# MCU.net
KiCad netlist of a schematic drawn in Altium Designer
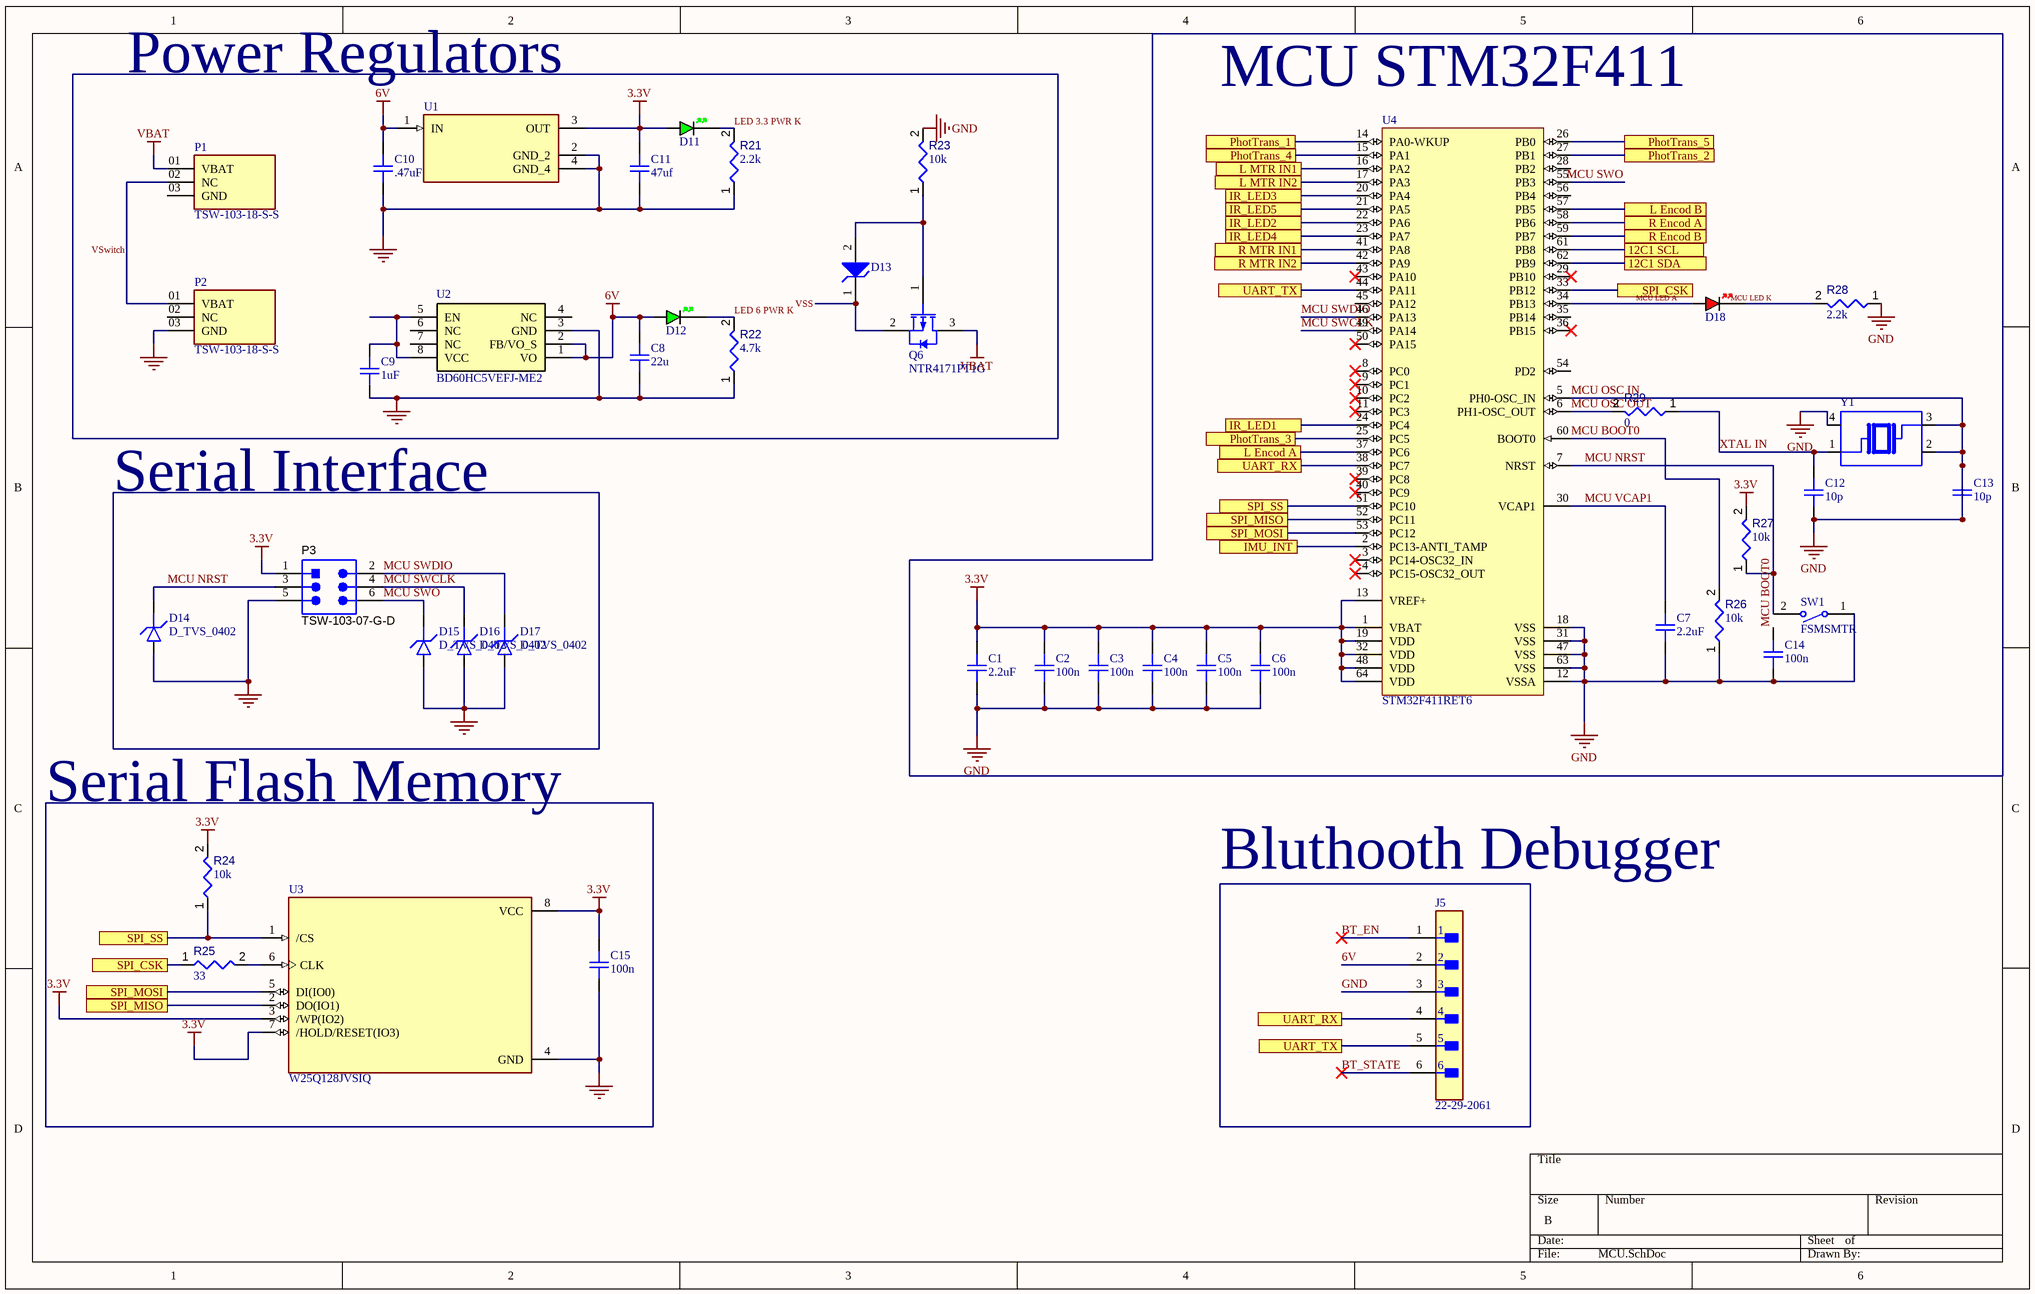
[diagram p0: MCU.SchDoc]

(export (version "E")
  (design (tool "Eeschema 10.0.6"))
  (components
    (comp (ref "C1")
      (value "2.2uF")
      (footprint "CAP_0603")
      (description "Capacitor SMD 0603")
      (libsource (lib "Schematic-Lib-PhilsLab") (part "CAP_0603"))
    )
    (comp (ref "C2")
      (value "100n")
      (footprint "CAP_0603")
      (description "Capacitor SMD 0603")
      (libsource (lib "Schematic-Lib-PhilsLab") (part "CAP_0603"))
    )
    (comp (ref "C3")
      (value "100n")
      (footprint "CAP_0603")
      (description "Capacitor SMD 0603")
      (libsource (lib "Schematic-Lib-PhilsLab") (part "CAP_0603"))
    )
    (comp (ref "C4")
      (value "100n")
      (footprint "CAP_0603")
      (description "Capacitor SMD 0603")
      (libsource (lib "Schematic-Lib-PhilsLab") (part "CAP_0603"))
    )
    (comp (ref "C5")
      (value "100n")
      (footprint "CAP_0603")
      (description "Capacitor SMD 0603")
      (libsource (lib "Schematic-Lib-PhilsLab") (part "CAP_0603"))
    )
    (comp (ref "C6")
      (value "100n")
      (footprint "CAP_0603")
      (description "Capacitor SMD 0603")
      (libsource (lib "Schematic-Lib-PhilsLab") (part "CAP_0603"))
    )
    (comp (ref "C7")
      (value "2.2uF")
      (footprint "CAP_0603")
      (description "Capacitor SMD 0603")
      (libsource (lib "Schematic-Lib-PhilsLab") (part "CAP_0603"))
    )
    (comp (ref "C8")
      (value "22u")
      (footprint "CAP_0805")
      (description "Capacitor SMD 0805")
      (libsource (lib "Schematic-Lib-PhilsLab") (part "CAP_0805"))
    )
    (comp (ref "C9")
      (value "1uF")
      (footprint "CAP_0603")
      (description "Capacitor SMD 0603")
      (libsource (lib "Schematic-Lib-PhilsLab") (part "CAP_0603"))
    )
    (comp (ref "C10")
      (value ".47uF")
      (footprint "CAP_0603")
      (description "Capacitor SMD 0603")
      (libsource (lib "Schematic-Lib-PhilsLab") (part "CAP_0603"))
    )
    (comp (ref "C11")
      (value "47uf")
      (footprint "CAP_1210")
      (description "Capacitor SMD 1210")
      (libsource (lib "Schematic-Lib-PhilsLab") (part "CAP_1210"))
    )
    (comp (ref "C12")
      (value "10p")
      (footprint "CAP_0603")
      (description "Capacitor SMD 0603")
      (libsource (lib "Schematic-Lib-PhilsLab") (part "CAP_0603"))
    )
    (comp (ref "C13")
      (value "10p")
      (footprint "CAP_0603")
      (description "Capacitor SMD 0603")
      (libsource (lib "Schematic-Lib-PhilsLab") (part "CAP_0603"))
    )
    (comp (ref "C14")
      (value "100n")
      (footprint "CAP_0603")
      (description "Capacitor SMD 0603")
      (libsource (lib "Schematic-Lib-PhilsLab") (part "CAP_0603"))
    )
    (comp (ref "C15")
      (value "100n")
      (footprint "CAP_0603")
      (description "Capacitor SMD 0603")
      (libsource (lib "Schematic-Lib-PhilsLab") (part "CAP_0603"))
    )
    (comp (ref "D11")
      (value "GREEN")
      (footprint "LED_0603_GREEN")
      (description "LED 0603 GREEN SMD")
      (libsource (lib "Schematic-Lib-PhilsLab") (part "LED_0603_GREEN"))
    )
    (comp (ref "D12")
      (value "GREEN")
      (footprint "LED_0603_GREEN")
      (description "LED 0603 GREEN SMD")
      (libsource (lib "Schematic-Lib-PhilsLab") (part "LED_0603_GREEN"))
    )
    (comp (ref "D13")
      (value "MMSZ4697T1G")
      (footprint "ONSC-SOD-123-2-425-04_V")
      (description "Zener Voltage Regulator, 500 mW, 2-Pin SOD-123, Pb-Free, Tape and Reel")
      (fields (field (name "MANUFACTURER") "On Semiconductor"))
      (libsource (lib "Altium Content Vault") (part "ONSC-K1A2-2"))
    )
    (comp (ref "D14")
      (value "D_TVS_0402")
      (footprint "D_0402")
      (description "Diode TVS / ESD 0402")
      (libsource (lib "Schematic-Lib-PhilsLab") (part "D_TVS_0402"))
    )
    (comp (ref "D15")
      (value "D_TVS_0402")
      (footprint "D_0402")
      (description "Diode TVS / ESD 0402")
      (libsource (lib "Schematic-Lib-PhilsLab") (part "D_TVS_0402"))
    )
    (comp (ref "D16")
      (value "D_TVS_0402")
      (footprint "D_0402")
      (description "Diode TVS / ESD 0402")
      (libsource (lib "Schematic-Lib-PhilsLab") (part "D_TVS_0402"))
    )
    (comp (ref "D17")
      (value "D_TVS_0402")
      (footprint "D_0402")
      (description "Diode TVS / ESD 0402")
      (libsource (lib "Schematic-Lib-PhilsLab") (part "D_TVS_0402"))
    )
    (comp (ref "D18")
      (value "RED")
      (footprint "LED_0603_RED")
      (description "LED 0603 RED SMD")
      (libsource (lib "Schematic-Lib-PhilsLab") (part "LED_0603_RED"))
    )
    (comp (ref "J5")
      (value "22-29-2061")
      (footprint "FP-22-29-2061-MFG")
      (description "CONN HEADER VERT 6POS 2.54MM")
      (libsource (lib "Altium Content Vault") (part "f2cb566baf1c37ab5a3b8e90bbeafd6"))
    )
    (comp (ref "P1")
      (value "TSW-103-18-S-S")
      (footprint "SAMTEC_TSW-103-18-S-S")
      (libsource (lib "Schematic-Lib-PhilsLab") (part "TSW-103-18-S-S"))
    )
    (comp (ref "P2")
      (value "TSW-103-18-S-S")
      (footprint "SAMTEC_TSW-103-18-S-S")
      (libsource (lib "Schematic-Lib-PhilsLab") (part "TSW-103-18-S-S"))
    )
    (comp (ref "P3")
      (value "TSW-103-07-G-D")
      (footprint "SMTC-TSW-103-07-G-D_V")
      (fields (field (name "MANUFACTURER") "Samtec-Inc."))
      (libsource (lib "Altium Content Vault") (part "CN-2P-M-R6"))
    )
    (comp (ref "Q6")
      (value "NTR4171PT1G")
      (footprint "ONSC-SOT-23-3-318-08_V")
      (description "Power MOSFET, -30 V, 3.5 A, Single P-Channel, 3-Pin SOT-23, Pb-Free, Tape and Reel")
      (fields (field (name "MANUFACTURER") "On Semiconductor"))
      (libsource (lib "Altium Content Vault") (part "ONSC-PMOS-G1S2D3-3_D"))
    )
    (comp (ref "R21")
      (value "2.2k")
      (footprint "RESC0402(1005)_L")
      (description "324K 0.063W 1% 0402 (1005 Metric)  SMD")
      (fields (field (name "TOLERANCE") "1%") (field (name "POWER") "63mW"))
      (libsource (lib "Edgar Restor") (part "324KR2F"))
    )
    (comp (ref "R22")
      (value "4.7k")
      (footprint "RESC0402(1005)_L")
      (description "324K 0.063W 1% 0402 (1005 Metric)  SMD")
      (fields (field (name "TOLERANCE") "1%") (field (name "POWER") "63mW"))
      (libsource (lib "Edgar Restor") (part "324KR2F"))
    )
    (comp (ref "R23")
      (value "10k")
      (footprint "RESC0402(1005)_L")
      (description "324K 0.063W 1% 0402 (1005 Metric)  SMD")
      (fields (field (name "TOLERANCE") "1%") (field (name "POWER") "63mW"))
      (libsource (lib "Edgar Restor") (part "324KR2F"))
    )
    (comp (ref "R24")
      (value "10k")
      (footprint "RESC0402(1005)_L")
      (description "324K 0.063W 1% 0402 (1005 Metric)  SMD")
      (fields (field (name "TOLERANCE") "1%") (field (name "POWER") "63mW"))
      (libsource (lib "Edgar Restor") (part "324KR2F"))
    )
    (comp (ref "R25")
      (value "33")
      (footprint "RESC0402(1005)_L")
      (description "324K 0.063W 1% 0402 (1005 Metric)  SMD")
      (fields (field (name "TOLERANCE") "1%") (field (name "POWER") "63mW"))
      (libsource (lib "Edgar Restor") (part "324KR2F"))
    )
    (comp (ref "R26")
      (value "10k")
      (footprint "RESC0402(1005)_L")
      (description "324K 0.063W 1% 0402 (1005 Metric)  SMD")
      (fields (field (name "TOLERANCE") "1%") (field (name "POWER") "63mW"))
      (libsource (lib "Edgar Restor") (part "324KR2F"))
    )
    (comp (ref "R27")
      (value "10k")
      (footprint "RESC0402(1005)_L")
      (description "324K 0.063W 1% 0402 (1005 Metric)  SMD")
      (fields (field (name "TOLERANCE") "1%") (field (name "POWER") "63mW"))
      (libsource (lib "Edgar Restor") (part "324KR2F"))
    )
    (comp (ref "R28")
      (value "2.2k")
      (footprint "RESC0402(1005)_L")
      (description "324K 0.063W 1% 0402 (1005 Metric)  SMD")
      (fields (field (name "TOLERANCE") "1%") (field (name "POWER") "63mW"))
      (libsource (lib "Edgar Restor") (part "324KR2F"))
    )
    (comp (ref "R29")
      (value "0")
      (footprint "RESC0402(1005)_L")
      (description "324K 0.063W 1% 0402 (1005 Metric)  SMD")
      (fields (field (name "TOLERANCE") "1%") (field (name "POWER") "63mW"))
      (libsource (lib "Edgar Restor") (part "324KR2F"))
    )
    (comp (ref "SW1")
      (value "FSMSMTR")
      (footprint "TECO-FSMSMTR_V")
      (description "FSMSM Push Button Switch, 50 mA, -35 to 85 degC, 2-Pin SMD, RoHS, Tape and Reel")
      (fields (field (name "MANUFACTURER") "TE Connectivity"))
      (libsource (lib "Altium Content Vault") (part "SW-SPST-2_C"))
    )
    (comp (ref "U1")
      (value "~")
      (footprint "LM3940IMP-3.3_NOPB:VREG_LM3940IMP-3.3/NOPB")
      (description "Ð›Ð¸Ð½ÐµÐ¹Ð½Ñ‹Ð¹ ÑÑ‚Ð°Ð±Ð¸Ð»Ð¸Ð·Ð°Ñ‚Ð¾Ñ€ Ð½Ð°Ð¿Ñ€ÑÐ¶ÐµÐ½Ð¸Ñ IC 1 Output 1A SOT-223-4")
      (fields (field (name "MP") "LM3940IMP33") (field (name "MF") "National Semiconductor"))
      (libsource (lib "LM3940IMP-3.3_NOPB") (part "LM3940IMP-3.3/NOPB"))
    )
    (comp (ref "U2")
      (value "BD60HC5VEFJ-ME2")
      (footprint "TSOP127P600X100_HS-9N")
      (description "Linear Voltage Regulator IC Positive Fixed 1 Output 1.5A 8-HTSOP-J")
      (fields (field (name "MANUFACTURER") "Rohm"))
      (libsource (lib "Schematic-Lib-PhilsLab") (part "BD60HC5VEFJ-ME2"))
    )
    (comp (ref "U3")
      (value "W25Q128JVSIQ")
      (footprint "SOIC127P790X216-8N")
      (description "FLASH - NOR Memory IC 128Mb (16M x 8) SPI - Quad I/O, QPI, DTR 133 MHz 8-SOIC")
      (fields (field (name "MF") "Winbond Electronics"))
      (libsource (lib "Edgar Restor") (part "W25Q128JVSIQ"))
    )
    (comp (ref "U4")
      (value "STM32F411RET6")
      (footprint "STM-LQFP64_L")
      (description "ARM Cortex-M4 32-bit MCU+FPU, 512 KB Flash, 128 KB RAM, 50 I/Os, 64-Pin LQFP, -40 to 85 degC, Tray")
      (libsource (lib "Altium Content Vault") (part "MC-ARM-STM32F411-LQFP64"))
    )
    (comp (ref "Y1")
      (value "TSX-322524.0000MF15X-AC3")
      (footprint "OSCCC320X250X60")
      (description "24MHz Â±10ppm Crystal 9pF 40 Ohms 4-SMD, No Lead")
      (fields (field (name "MF") "EPSON") (field (name "MP") "TSX-3225 24.0000MF15X-AC3"))
      (libsource (lib "SnapEDAsch") (part "TSX-322524.0000MF15X-AC3"))
    )
  )
  (nets
    (net (code "1") (name "/12C1 SCL") (class "Default")
      (node (ref "U4") (pin "61") (pinfunction "PB8_61") (pintype "bidirectional"))
    )
    (net (code "2") (name "/12C1 SDA") (class "Default")
      (node (ref "U4") (pin "62") (pinfunction "PB9_62") (pintype "bidirectional"))
    )
    (net (code "3") (name "/BT_EN") (class "Default")
      (node (ref "J5") (pin "1") (pinfunction "1_1") (pintype "passive+no_connect"))
    )
    (net (code "4") (name "/BT_STATE") (class "Default")
      (node (ref "J5") (pin "6") (pinfunction "6_6") (pintype "passive+no_connect"))
    )
    (net (code "5") (name "/IMU_INT") (class "Default")
      (node (ref "U4") (pin "2") (pinfunction "PC13-ANTI_TAMP_2") (pintype "bidirectional"))
    )
    (net (code "6") (name "/IR_LED1") (class "Default")
      (node (ref "U4") (pin "24") (pinfunction "PC4_24") (pintype "bidirectional"))
    )
    (net (code "7") (name "/IR_LED2") (class "Default")
      (node (ref "U4") (pin "22") (pinfunction "PA6_22") (pintype "bidirectional"))
    )
    (net (code "8") (name "/IR_LED3") (class "Default")
      (node (ref "U4") (pin "20") (pinfunction "PA4_20") (pintype "bidirectional"))
    )
    (net (code "9") (name "/IR_LED4") (class "Default")
      (node (ref "U4") (pin "23") (pinfunction "PA7_23") (pintype "bidirectional"))
    )
    (net (code "10") (name "/IR_LED5") (class "Default")
      (node (ref "U4") (pin "21") (pinfunction "PA5_21") (pintype "bidirectional"))
    )
    (net (code "11") (name "/L Encod A") (class "Default")
      (node (ref "U4") (pin "37") (pinfunction "PC6_37") (pintype "bidirectional"))
    )
    (net (code "12") (name "/L Encod B") (class "Default")
      (node (ref "U4") (pin "57") (pinfunction "PB5_57") (pintype "bidirectional"))
    )
    (net (code "13") (name "/L MTR IN1") (class "Default")
      (node (ref "U4") (pin "16") (pinfunction "PA2_16") (pintype "bidirectional"))
    )
    (net (code "14") (name "/L MTR IN2") (class "Default")
      (node (ref "U4") (pin "17") (pinfunction "PA3_17") (pintype "bidirectional"))
    )
    (net (code "15") (name "/LED 3.3 PWR K") (class "Default")
      (node (ref "D11") (pin "K") (pinfunction "K_K") (pintype "passive"))
      (node (ref "R21") (pin "2") (pinfunction "2_2") (pintype "passive"))
    )
    (net (code "16") (name "/LED 6 PWR K") (class "Default")
      (node (ref "D12") (pin "K") (pinfunction "K_K") (pintype "passive"))
      (node (ref "R22") (pin "2") (pinfunction "2_2") (pintype "passive"))
    )
    (net (code "17") (name "/MCU BOOT0") (class "Default")
      (node (ref "C14") (pin "2") (pinfunction "2_2") (pintype "passive"))
      (node (ref "R26") (pin "2") (pinfunction "2_2") (pintype "passive"))
      (node (ref "U4") (pin "60") (pinfunction "BOOT0_60") (pintype "input"))
    )
    (net (code "18") (name "/MCU LED A") (class "Default")
      (node (ref "D18") (pin "A") (pinfunction "A_A") (pintype "passive"))
      (node (ref "U4") (pin "34") (pinfunction "PB13_34") (pintype "bidirectional"))
    )
    (net (code "19") (name "/MCU LED K") (class "Default")
      (node (ref "D18") (pin "K") (pinfunction "K_K") (pintype "passive"))
      (node (ref "R28") (pin "2") (pinfunction "2_2") (pintype "passive"))
    )
    (net (code "20") (name "/MCU NRST") (class "Default")
      (node (ref "D14") (pin "K") (pinfunction "K_K") (pintype "passive"))
      (node (ref "P3") (pin "3") (pinfunction "3_3") (pintype "passive"))
      (node (ref "R27") (pin "1") (pinfunction "1_1") (pintype "passive"))
      (node (ref "SW1") (pin "2") (pinfunction "2_2") (pintype "passive"))
      (node (ref "U4") (pin "7") (pinfunction "NRST_7") (pintype "bidirectional"))
    )
    (net (code "21") (name "/MCU OSC OUT") (class "Default")
      (node (ref "R29") (pin "2") (pinfunction "2_2") (pintype "passive"))
      (node (ref "U4") (pin "6") (pinfunction "PH1-OSC_OUT_6") (pintype "bidirectional"))
    )
    (net (code "22") (name "/MCU SWCLK") (class "Default")
      (node (ref "D16") (pin "K") (pinfunction "K_K") (pintype "passive"))
      (node (ref "P3") (pin "4") (pinfunction "4_4") (pintype "passive"))
      (node (ref "U4") (pin "49") (pinfunction "PA14_49") (pintype "bidirectional"))
    )
    (net (code "23") (name "/MCU SWDIO") (class "Default")
      (node (ref "D17") (pin "K") (pinfunction "K_K") (pintype "passive"))
      (node (ref "P3") (pin "2") (pinfunction "2_2") (pintype "passive"))
      (node (ref "U4") (pin "46") (pinfunction "PA13_46") (pintype "bidirectional"))
    )
    (net (code "24") (name "/MCU SWO") (class "Default")
      (node (ref "D15") (pin "K") (pinfunction "K_K") (pintype "passive"))
      (node (ref "P3") (pin "6") (pinfunction "6_6") (pintype "passive"))
      (node (ref "U4") (pin "55") (pinfunction "PB3_55") (pintype "bidirectional"))
    )
    (net (code "25") (name "/MCU VCAP1") (class "Default")
      (node (ref "C7") (pin "2") (pinfunction "2_2") (pintype "passive"))
      (node (ref "U4") (pin "30") (pinfunction "VCAP1_30") (pintype "passive"))
    )
    (net (code "26") (name "/PhotTrans_1") (class "Default")
      (node (ref "U4") (pin "14") (pinfunction "PA0-WKUP_14") (pintype "bidirectional"))
    )
    (net (code "27") (name "/PhotTrans_2") (class "Default")
      (node (ref "U4") (pin "27") (pinfunction "PB1_27") (pintype "bidirectional"))
    )
    (net (code "28") (name "/PhotTrans_3") (class "Default")
      (node (ref "U4") (pin "25") (pinfunction "PC5_25") (pintype "bidirectional"))
    )
    (net (code "29") (name "/PhotTrans_4") (class "Default")
      (node (ref "U4") (pin "15") (pinfunction "PA1_15") (pintype "bidirectional"))
    )
    (net (code "30") (name "/PhotTrans_5") (class "Default")
      (node (ref "U4") (pin "26") (pinfunction "PB0_26") (pintype "bidirectional"))
    )
    (net (code "31") (name "/R Encod A") (class "Default")
      (node (ref "U4") (pin "58") (pinfunction "PB6_58") (pintype "bidirectional"))
    )
    (net (code "32") (name "/R Encod B") (class "Default")
      (node (ref "U4") (pin "59") (pinfunction "PB7_59") (pintype "bidirectional"))
    )
    (net (code "33") (name "/R MTR IN1") (class "Default")
      (node (ref "U4") (pin "41") (pinfunction "PA8_41") (pintype "bidirectional"))
    )
    (net (code "34") (name "/R MTR IN2") (class "Default")
      (node (ref "U4") (pin "42") (pinfunction "PA9_42") (pintype "bidirectional"))
    )
    (net (code "35") (name "/SPI_CSK") (class "Default")
      (node (ref "R25") (pin "1") (pinfunction "1_1") (pintype "passive"))
      (node (ref "U4") (pin "33") (pinfunction "PB12_33") (pintype "bidirectional"))
    )
    (net (code "36") (name "/SPI_MISO") (class "Default")
      (node (ref "U3") (pin "2") (pinfunction "DO(IO1)_2") (pintype "bidirectional"))
      (node (ref "U4") (pin "52") (pinfunction "PC11_52") (pintype "bidirectional"))
    )
    (net (code "37") (name "/SPI_MOSI") (class "Default")
      (node (ref "U3") (pin "5") (pinfunction "DI(IO0)_5") (pintype "bidirectional"))
      (node (ref "U4") (pin "53") (pinfunction "PC12_53") (pintype "bidirectional"))
    )
    (net (code "38") (name "/SPI_SS") (class "Default")
      (node (ref "R24") (pin "1") (pinfunction "1_1") (pintype "passive"))
      (node (ref "U3") (pin "1") (pinfunction "/CS_1") (pintype "input"))
      (node (ref "U4") (pin "51") (pinfunction "PC10_51") (pintype "bidirectional"))
    )
    (net (code "39") (name "/UART_RX") (class "Default")
      (node (ref "J5") (pin "4") (pinfunction "4_4") (pintype "passive"))
      (node (ref "U4") (pin "38") (pinfunction "PC7_38") (pintype "bidirectional"))
    )
    (net (code "40") (name "/UART_TX") (class "Default")
      (node (ref "J5") (pin "5") (pinfunction "5_5") (pintype "passive"))
      (node (ref "U4") (pin "44") (pinfunction "PA11_44") (pintype "bidirectional"))
    )
    (net (code "41") (name "/VSS") (class "Default")
      (node (ref "D13") (pin "1") (pinfunction "K_1") (pintype "passive"))
      (node (ref "Q6") (pin "2") (pinfunction "S_2") (pintype "passive"))
    )
    (net (code "42") (name "/VSwitch") (class "Default")
      (node (ref "P1") (pin "02") (pinfunction "NC_02") (pintype "passive"))
      (node (ref "P2") (pin "01") (pinfunction "VBAT_01") (pintype "passive"))
    )
    (net (code "43") (name "/XTAL IN") (class "Default")
      (node (ref "C12") (pin "2") (pinfunction "2_2") (pintype "passive"))
      (node (ref "R29") (pin "1") (pinfunction "1_1") (pintype "passive"))
      (node (ref "Y1") (pin "1") (pinfunction "1_1") (pintype "passive"))
    )
    (net (code "44") (name "3.3V") (class "Default")
      (node (ref "C1") (pin "2") (pinfunction "2_2") (pintype "passive"))
      (node (ref "C11") (pin "2") (pinfunction "2_2") (pintype "passive"))
      (node (ref "C15") (pin "2") (pinfunction "2_2") (pintype "passive"))
      (node (ref "C2") (pin "2") (pinfunction "2_2") (pintype "passive"))
      (node (ref "C3") (pin "2") (pinfunction "2_2") (pintype "passive"))
      (node (ref "C4") (pin "2") (pinfunction "2_2") (pintype "passive"))
      (node (ref "C5") (pin "2") (pinfunction "2_2") (pintype "passive"))
      (node (ref "C6") (pin "2") (pinfunction "2_2") (pintype "passive"))
      (node (ref "D11") (pin "A") (pinfunction "A_A") (pintype "passive"))
      (node (ref "P3") (pin "1") (pinfunction "1_1") (pintype "passive"))
      (node (ref "R24") (pin "2") (pinfunction "2_2") (pintype "passive"))
      (node (ref "R27") (pin "2") (pinfunction "2_2") (pintype "passive"))
      (node (ref "U1") (pin "3") (pinfunction "OUT_3") (pintype "power_in"))
      (node (ref "U3") (pin "3") (pinfunction "/WP(IO2)_3") (pintype "bidirectional"))
      (node (ref "U3") (pin "7") (pinfunction "/HOLD/RESET(IO3)_7") (pintype "bidirectional"))
      (node (ref "U3") (pin "8") (pinfunction "VCC_8") (pintype "power_in"))
      (node (ref "U4") (pin "1") (pinfunction "VBAT_1") (pintype "power_in"))
      (node (ref "U4") (pin "13") (pinfunction "VREF+_13") (pintype "power_in"))
      (node (ref "U4") (pin "19") (pinfunction "VDD_19") (pintype "power_in"))
      (node (ref "U4") (pin "32") (pinfunction "VDD_32") (pintype "power_in"))
      (node (ref "U4") (pin "48") (pinfunction "VDD_48") (pintype "power_in"))
      (node (ref "U4") (pin "64") (pinfunction "VDD_64") (pintype "power_in"))
    )
    (net (code "45") (name "6V") (class "Default")
      (node (ref "C10") (pin "2") (pinfunction "2_2") (pintype "passive"))
      (node (ref "C8") (pin "2") (pinfunction "2_2") (pintype "passive"))
      (node (ref "D12") (pin "A") (pinfunction "A_A") (pintype "passive"))
      (node (ref "J5") (pin "2") (pinfunction "2_2") (pintype "passive"))
      (node (ref "U1") (pin "1") (pinfunction "IN_1") (pintype "input"))
      (node (ref "U2") (pin "1") (pinfunction "VO_1") (pintype "passive"))
      (node (ref "U2") (pin "2") (pinfunction "FB/VO_S_2") (pintype "passive"))
    )
    (net (code "46") (name "GND") (class "Default")
      (node (ref "C1") (pin "1") (pinfunction "1_1") (pintype "passive"))
      (node (ref "C10") (pin "1") (pinfunction "1_1") (pintype "passive"))
      (node (ref "C11") (pin "1") (pinfunction "1_1") (pintype "passive"))
      (node (ref "C12") (pin "1") (pinfunction "1_1") (pintype "passive"))
      (node (ref "C13") (pin "1") (pinfunction "1_1") (pintype "passive"))
      (node (ref "C13") (pin "2") (pinfunction "2_2") (pintype "passive"))
      (node (ref "C14") (pin "1") (pinfunction "1_1") (pintype "passive"))
      (node (ref "C15") (pin "1") (pinfunction "1_1") (pintype "passive"))
      (node (ref "C2") (pin "1") (pinfunction "1_1") (pintype "passive"))
      (node (ref "C3") (pin "1") (pinfunction "1_1") (pintype "passive"))
      (node (ref "C4") (pin "1") (pinfunction "1_1") (pintype "passive"))
      (node (ref "C5") (pin "1") (pinfunction "1_1") (pintype "passive"))
      (node (ref "C6") (pin "1") (pinfunction "1_1") (pintype "passive"))
      (node (ref "C7") (pin "1") (pinfunction "1_1") (pintype "passive"))
      (node (ref "C8") (pin "1") (pinfunction "1_1") (pintype "passive"))
      (node (ref "C9") (pin "1") (pinfunction "1_1") (pintype "passive"))
      (node (ref "D14") (pin "A") (pinfunction "A_A") (pintype "passive"))
      (node (ref "D15") (pin "A") (pinfunction "A_A") (pintype "passive"))
      (node (ref "D16") (pin "A") (pinfunction "A_A") (pintype "passive"))
      (node (ref "D17") (pin "A") (pinfunction "A_A") (pintype "passive"))
      (node (ref "J5") (pin "3") (pinfunction "3_3") (pintype "passive"))
      (node (ref "P2") (pin "03") (pinfunction "GND_03") (pintype "passive"))
      (node (ref "P3") (pin "5") (pinfunction "5_5") (pintype "passive"))
      (node (ref "R21") (pin "1") (pinfunction "1_1") (pintype "passive"))
      (node (ref "R22") (pin "1") (pinfunction "1_1") (pintype "passive"))
      (node (ref "R23") (pin "2") (pinfunction "2_2") (pintype "passive"))
      (node (ref "R26") (pin "1") (pinfunction "1_1") (pintype "passive"))
      (node (ref "R28") (pin "1") (pinfunction "1_1") (pintype "passive"))
      (node (ref "SW1") (pin "1") (pinfunction "1_1") (pintype "passive"))
      (node (ref "U1") (pin "2") (pinfunction "GND_2_2") (pintype "power_in"))
      (node (ref "U1") (pin "4") (pinfunction "GND_4_4") (pintype "power_in"))
      (node (ref "U2") (pin "3") (pinfunction "GND_3") (pintype "passive"))
      (node (ref "U3") (pin "4") (pinfunction "GND_4") (pintype "power_in"))
      (node (ref "U4") (pin "12") (pinfunction "VSSA_12") (pintype "power_in"))
      (node (ref "U4") (pin "18") (pinfunction "VSS_18") (pintype "power_in"))
      (node (ref "U4") (pin "31") (pinfunction "VSS_31") (pintype "power_in"))
      (node (ref "U4") (pin "47") (pinfunction "VSS_47") (pintype "power_in"))
      (node (ref "U4") (pin "5") (pinfunction "PH0-OSC_IN_5") (pintype "bidirectional"))
      (node (ref "U4") (pin "63") (pinfunction "VSS_63") (pintype "power_in"))
      (node (ref "Y1") (pin "2") (pinfunction "2_2") (pintype "passive"))
      (node (ref "Y1") (pin "3") (pinfunction "3_3") (pintype "passive"))
      (node (ref "Y1") (pin "4") (pinfunction "4_4") (pintype "passive"))
    )
    (net (code "47") (name "Net-(D13-A)") (class "Default")
      (node (ref "D13") (pin "2") (pinfunction "A_2") (pintype "passive"))
      (node (ref "Q6") (pin "1") (pinfunction "G_1") (pintype "passive"))
      (node (ref "R23") (pin "1") (pinfunction "1_1") (pintype "passive"))
    )
    (net (code "48") (name "Net-(U2-EN)") (class "Default")
      (node (ref "C9") (pin "2") (pinfunction "2_2") (pintype "passive"))
      (node (ref "U2") (pin "5") (pinfunction "EN_5") (pintype "passive"))
      (node (ref "U2") (pin "8") (pinfunction "VCC_8") (pintype "passive"))
    )
    (net (code "49") (name "Net-(U3-CLK)") (class "Default")
      (node (ref "R25") (pin "2") (pinfunction "2_2") (pintype "passive"))
      (node (ref "U3") (pin "6") (pinfunction "CLK_6") (pintype "input"))
    )
    (net (code "50") (name "VBAT") (class "Default")
      (node (ref "P1") (pin "01") (pinfunction "VBAT_01") (pintype "passive"))
      (node (ref "Q6") (pin "3") (pinfunction "D_3") (pintype "passive"))
    )
    (net (code "51") (name "unconnected-(P1-GND-Pad03)") (class "Default")
      (node (ref "P1") (pin "03") (pinfunction "GND_03") (pintype "passive"))
    )
    (net (code "52") (name "unconnected-(P2-NC-Pad02)") (class "Default")
      (node (ref "P2") (pin "02") (pinfunction "NC_02") (pintype "passive"))
    )
    (net (code "53") (name "unconnected-(U2-NC-Pad4)") (class "Default")
      (node (ref "U2") (pin "4") (pinfunction "NC_4") (pintype "passive"))
    )
    (net (code "54") (name "unconnected-(U2-NC-Pad6)") (class "Default")
      (node (ref "U2") (pin "6") (pinfunction "NC_6") (pintype "passive"))
    )
    (net (code "55") (name "unconnected-(U2-NC-Pad7)") (class "Default")
      (node (ref "U2") (pin "7") (pinfunction "NC_7") (pintype "passive"))
    )
    (net (code "56") (name "unconnected-(U4-PA10-Pad43)") (class "Default")
      (node (ref "U4") (pin "43") (pinfunction "PA10_43") (pintype "bidirectional+no_connect"))
    )
    (net (code "57") (name "unconnected-(U4-PA12-Pad45)") (class "Default")
      (node (ref "U4") (pin "45") (pinfunction "PA12_45") (pintype "bidirectional"))
    )
    (net (code "58") (name "unconnected-(U4-PA15-Pad50)") (class "Default")
      (node (ref "U4") (pin "50") (pinfunction "PA15_50") (pintype "bidirectional+no_connect"))
    )
    (net (code "59") (name "unconnected-(U4-PB2-Pad28)") (class "Default")
      (node (ref "U4") (pin "28") (pinfunction "PB2_28") (pintype "bidirectional"))
    )
    (net (code "60") (name "unconnected-(U4-PB4-Pad56)") (class "Default")
      (node (ref "U4") (pin "56") (pinfunction "PB4_56") (pintype "bidirectional"))
    )
    (net (code "61") (name "unconnected-(U4-PB10-Pad29)") (class "Default")
      (node (ref "U4") (pin "29") (pinfunction "PB10_29") (pintype "bidirectional+no_connect"))
    )
    (net (code "62") (name "unconnected-(U4-PB14-Pad35)") (class "Default")
      (node (ref "U4") (pin "35") (pinfunction "PB14_35") (pintype "bidirectional"))
    )
    (net (code "63") (name "unconnected-(U4-PB15-Pad36)") (class "Default")
      (node (ref "U4") (pin "36") (pinfunction "PB15_36") (pintype "bidirectional+no_connect"))
    )
    (net (code "64") (name "unconnected-(U4-PC0-Pad8)") (class "Default")
      (node (ref "U4") (pin "8") (pinfunction "PC0_8") (pintype "bidirectional+no_connect"))
    )
    (net (code "65") (name "unconnected-(U4-PC1-Pad9)") (class "Default")
      (node (ref "U4") (pin "9") (pinfunction "PC1_9") (pintype "bidirectional+no_connect"))
    )
    (net (code "66") (name "unconnected-(U4-PC2-Pad10)") (class "Default")
      (node (ref "U4") (pin "10") (pinfunction "PC2_10") (pintype "bidirectional+no_connect"))
    )
    (net (code "67") (name "unconnected-(U4-PC3-Pad11)") (class "Default")
      (node (ref "U4") (pin "11") (pinfunction "PC3_11") (pintype "bidirectional+no_connect"))
    )
    (net (code "68") (name "unconnected-(U4-PC8-Pad39)") (class "Default")
      (node (ref "U4") (pin "39") (pinfunction "PC8_39") (pintype "bidirectional+no_connect"))
    )
    (net (code "69") (name "unconnected-(U4-PC9-Pad40)") (class "Default")
      (node (ref "U4") (pin "40") (pinfunction "PC9_40") (pintype "bidirectional+no_connect"))
    )
    (net (code "70") (name "unconnected-(U4-PC14-OSC32_IN-Pad3)") (class "Default")
      (node (ref "U4") (pin "3") (pinfunction "PC14-OSC32_IN_3") (pintype "bidirectional+no_connect"))
    )
    (net (code "71") (name "unconnected-(U4-PC15-OSC32_OUT-Pad4)") (class "Default")
      (node (ref "U4") (pin "4") (pinfunction "PC15-OSC32_OUT_4") (pintype "bidirectional+no_connect"))
    )
    (net (code "72") (name "unconnected-(U4-PD2-Pad54)") (class "Default")
      (node (ref "U4") (pin "54") (pinfunction "PD2_54") (pintype "bidirectional"))
    )
  )
)
